# UVA_Module.net
KiCad netlist of a schematic drawn in EAGLE
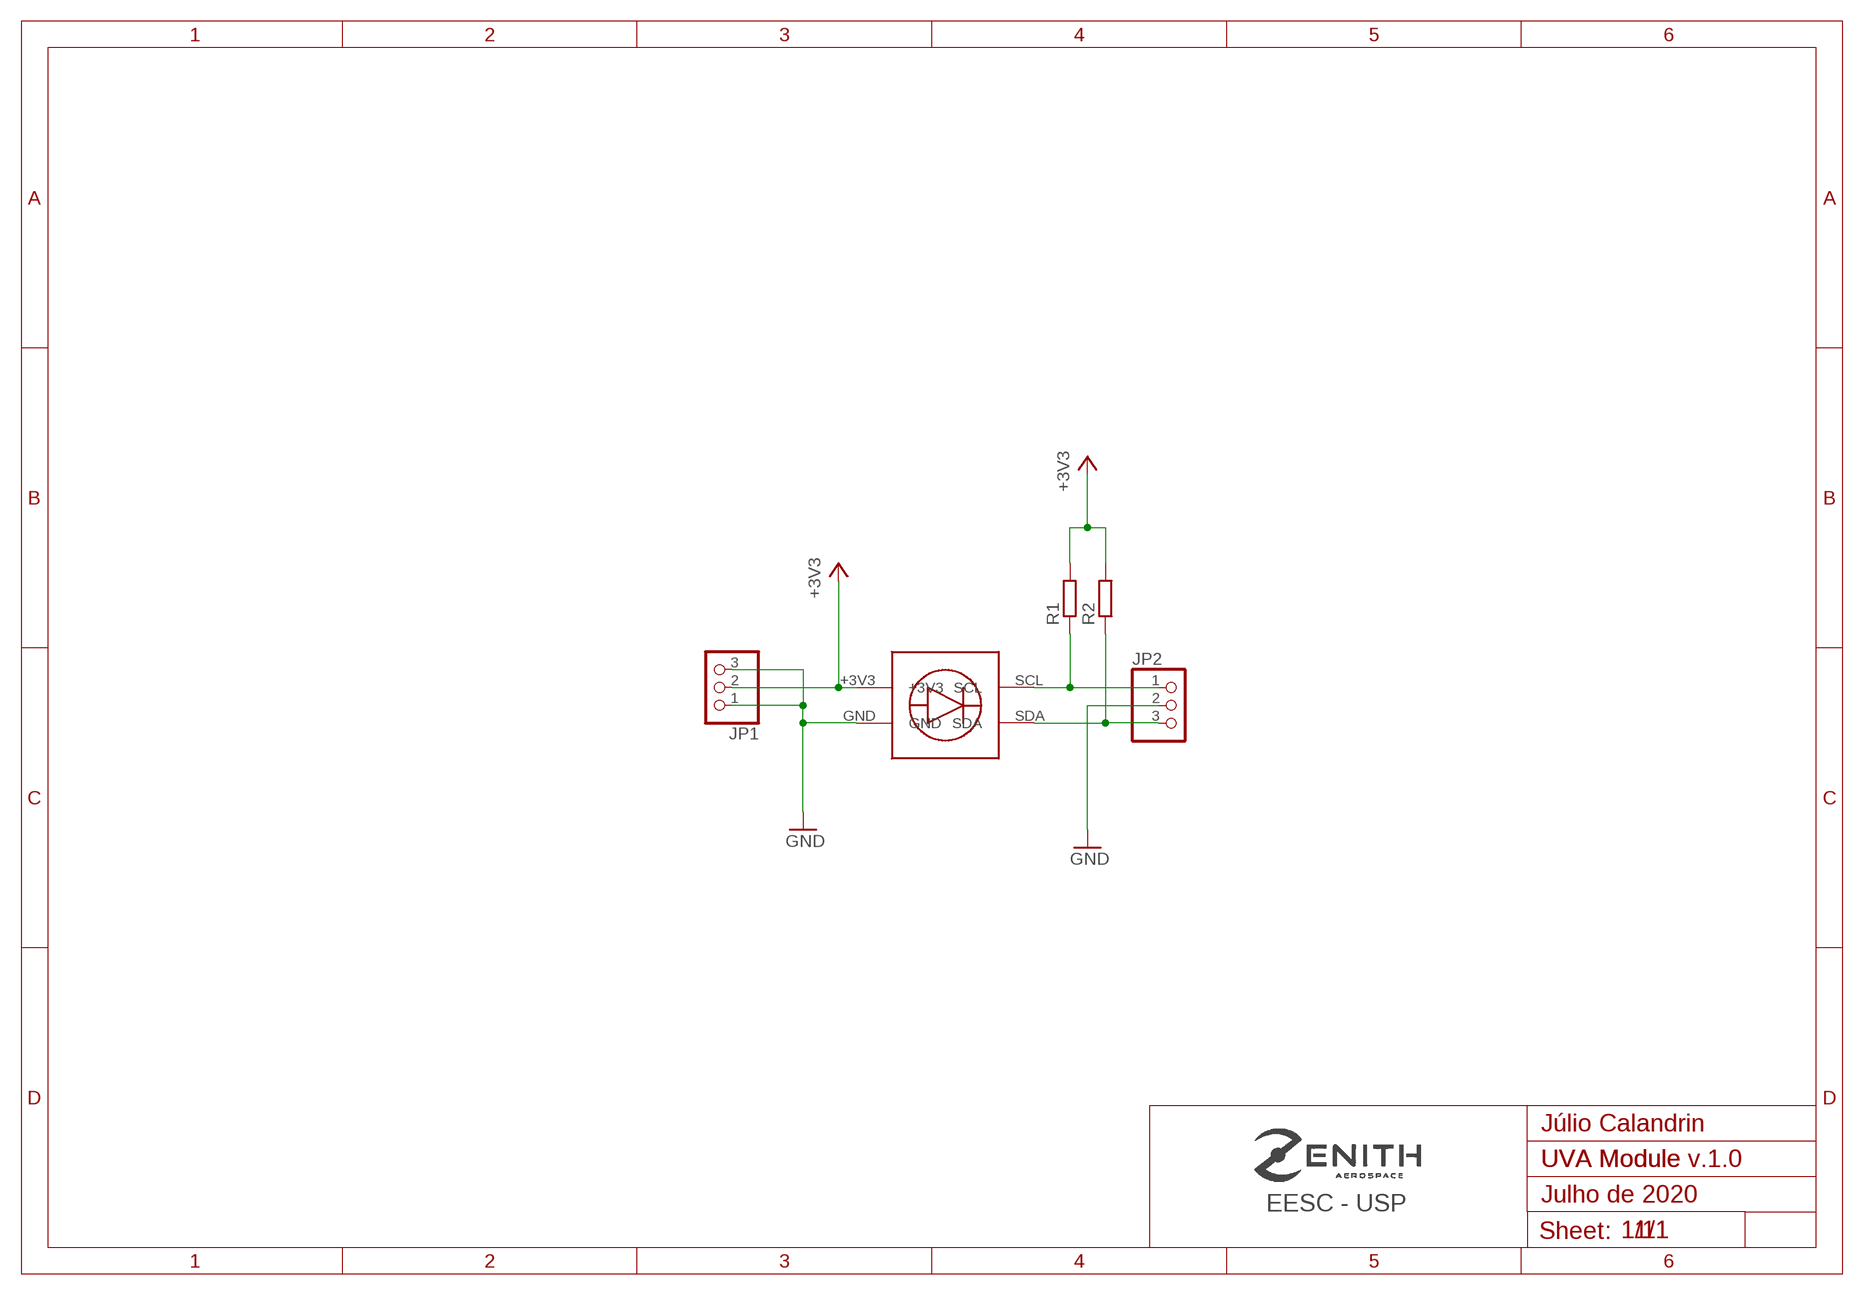
[diagram p0: schematic, sheet 1]

(export (version "E")
  (design (tool "Eeschema 10.0.6"))
  (components
    (comp (ref "JP1")
      (value "PINHD-1X3")
      (footprint "eagle-import:1X03")
      (libsource (lib "eagle-import") (part "PINHD-1X3"))
    )
    (comp (ref "JP2")
      (value "PINHD-1X3")
      (footprint "eagle-import:1X03")
      (libsource (lib "eagle-import") (part "PINHD-1X3"))
    )
    (comp (ref "R1")
      (value "R-EU_R0805")
      (footprint "eagle-import:R0805")
      (libsource (lib "eagle-import") (part "R-EU_R0805"))
    )
    (comp (ref "R2")
      (value "R-EU_R0805")
      (footprint "eagle-import:R0805")
      (libsource (lib "eagle-import") (part "R-EU_R0805"))
    )
    (comp (ref "U$1")
      (value "BREAKOUT_UV-A")
      (footprint "eagle-import:PADS_UV-A_B")
      (libsource (lib "eagle-import") (part "BREAKOUT_UV-A"))
    )
  )
  (nets
    (net (code "1") (name "+3V3") (class "Default")
      (node (ref "JP1") (pin "2") (pinfunction "2_2") (pintype "passive"))
      (node (ref "R1") (pin "2") (pinfunction "2_2") (pintype "passive"))
      (node (ref "R2") (pin "2") (pinfunction "2_2") (pintype "passive"))
      (node (ref "U$1") (pin "+3V3") (pinfunction "+3V3_+3V3") (pintype "bidirectional"))
    )
    (net (code "2") (name "GND") (class "Default")
      (node (ref "JP1") (pin "1") (pinfunction "1_1") (pintype "passive"))
      (node (ref "JP1") (pin "3") (pinfunction "3_3") (pintype "passive"))
      (node (ref "JP2") (pin "2") (pinfunction "2_2") (pintype "passive"))
      (node (ref "U$1") (pin "GND") (pinfunction "GND_GND") (pintype "bidirectional"))
    )
    (net (code "3") (name "Net-(JP2-Pad1)") (class "Default")
      (node (ref "JP2") (pin "1") (pinfunction "1_1") (pintype "passive"))
      (node (ref "R1") (pin "1") (pinfunction "1_1") (pintype "passive"))
      (node (ref "U$1") (pin "SCL") (pinfunction "SCL_SCL") (pintype "bidirectional"))
    )
    (net (code "4") (name "Net-(JP2-Pad3)") (class "Default")
      (node (ref "JP2") (pin "3") (pinfunction "3_3") (pintype "passive"))
      (node (ref "R2") (pin "1") (pinfunction "1_1") (pintype "passive"))
      (node (ref "U$1") (pin "SDA") (pinfunction "SDA_SDA") (pintype "bidirectional"))
    )
  )
)
